# Conectores.net
KiCad netlist of a schematic drawn in Altium Designer
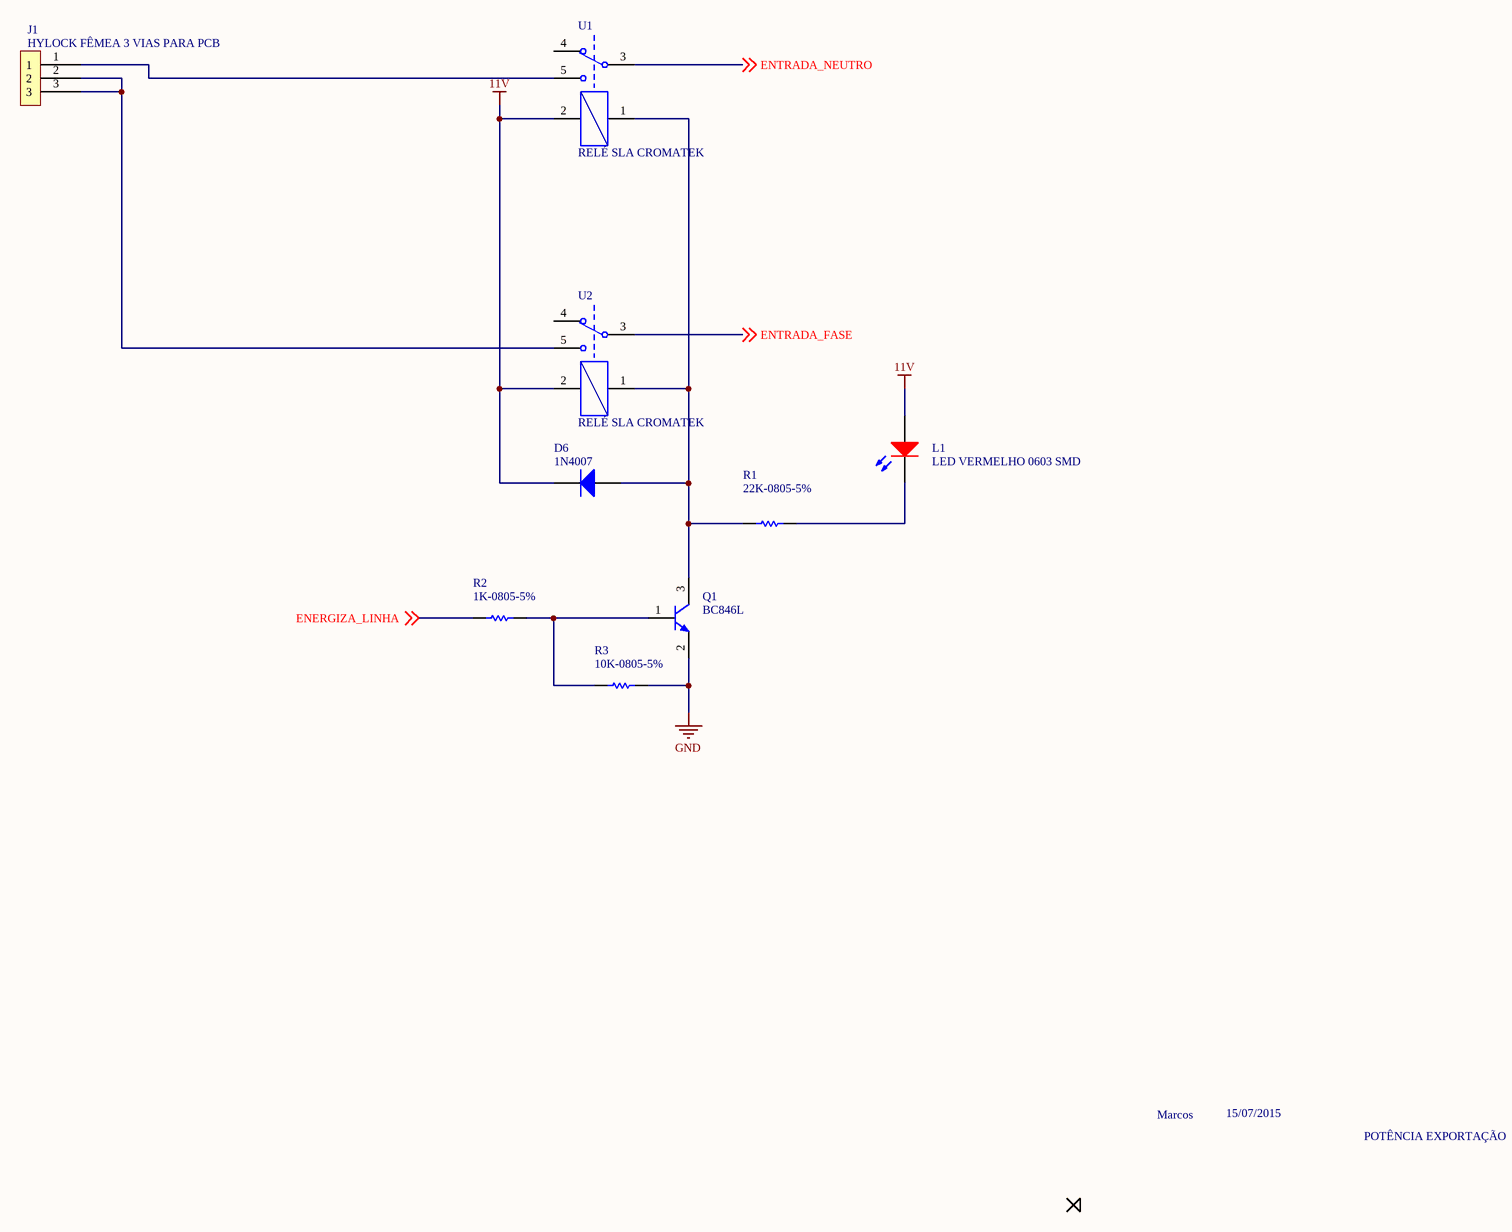
[diagram p0: Conectores.SchDoc]

(export (version "E")
  (design (tool "Eeschema 10.0.6"))
  (components
    (comp (ref "D6") (value "1N4007") (footprint "SMA DIODES") (libsource (lib "AquinoLib") (part "1N4007")))
    (comp (ref "J1")
      (value "HYLOCK FÊMEA 3 VIAS PARA PCB")
      (footprint "CONECTOR HYLOCK 3 VIAS")
      (description "PCMC2-3")
      (libsource (lib "AquinoLib") (part "PCMC2-3"))
    )
    (comp (ref "L1")
      (value "LED VERMELHO 0603 SMD")
      (footprint "LED 1206")
      (libsource (lib "AquinoLib") (part "LED VERMELHO 0603 SMD"))
    )
    (comp (ref "Q1")
      (value "BC846L")
      (footprint "SOT23 - REVISADO ONDA")
      (libsource (lib "AquinoLib") (part "BC846"))
    )
    (comp (ref "R1")
      (value "22K-0805-5%")
      (footprint "0805-REVISADO ONDA")
      (libsource (lib "AquinoLib") (part "22K-0805-5%"))
    )
    (comp (ref "R2")
      (value "1K-0805-5%")
      (footprint "0805-REVISADO ONDA")
      (description "10K-0805-5%")
      (libsource (lib "AquinoLib") (part "10K-0805-5%"))
    )
    (comp (ref "R3")
      (value "10K-0805-5%")
      (footprint "0805-REVISADO ONDA")
      (libsource (lib "AquinoLib") (part "10K-0805-5%"))
    )
    (comp (ref "U1")
      (value "RELÉ SLA CROMATEK")
      (footprint "RELE SLA CROMATEK")
      (libsource (lib "AquinoLib") (part "RELÉ SLA CROMATEK"))
    )
    (comp (ref "U2")
      (value "RELÉ SLA CROMATEK")
      (footprint "RELE SLA CROMATEK")
      (libsource (lib "AquinoLib") (part "RELÉ SLA CROMATEK"))
    )
  )
  (nets
    (net (code "1") (name "11V") (class "Default")
      (node (ref "D6") (pin "2") (pinfunction "K_2") (pintype "passive"))
      (node (ref "L1") (pin "1") (pinfunction "A_1") (pintype "passive"))
      (node (ref "U1") (pin "2") (pinfunction "A2_2") (pintype "passive"))
      (node (ref "U2") (pin "2") (pinfunction "A2_2") (pintype "passive"))
    )
    (net (code "2") (name "ENERGIZA_LINHA") (class "Default")
      (node (ref "R2") (pin "1") (pinfunction "1_1") (pintype "passive"))
    )
    (net (code "3") (name "ENTRADA_FASE") (class "Default")
      (node (ref "U2") (pin "3") (pinfunction "3_3") (pintype "passive"))
    )
    (net (code "4") (name "ENTRADA_NEUTRO") (class "Default")
      (node (ref "U1") (pin "3") (pinfunction "3_3") (pintype "passive"))
    )
    (net (code "5") (name "GND") (class "Default")
      (node (ref "Q1") (pin "2") (pinfunction "E_2") (pintype "passive"))
      (node (ref "R3") (pin "2") (pinfunction "2_2") (pintype "passive"))
    )
    (net (code "6") (name "Net-(D6-A)") (class "Default")
      (node (ref "D6") (pin "1") (pinfunction "A_1") (pintype "passive"))
      (node (ref "Q1") (pin "3") (pinfunction "C_3") (pintype "passive"))
      (node (ref "R1") (pin "1") (pinfunction "1_1") (pintype "passive"))
      (node (ref "U1") (pin "1") (pinfunction "A1_1") (pintype "passive"))
      (node (ref "U2") (pin "1") (pinfunction "A1_1") (pintype "passive"))
    )
    (net (code "7") (name "Net-(J1-Pad1)") (class "Default")
      (node (ref "J1") (pin "1") (pinfunction "1_1") (pintype "passive"))
      (node (ref "U1") (pin "5") (pinfunction "5_5") (pintype "passive"))
    )
    (net (code "8") (name "Net-(J1-Pad2)") (class "Default")
      (node (ref "J1") (pin "2") (pinfunction "2_2") (pintype "passive"))
      (node (ref "J1") (pin "3") (pinfunction "3_3") (pintype "passive"))
      (node (ref "U2") (pin "5") (pinfunction "5_5") (pintype "passive"))
    )
    (net (code "9") (name "Net-(L1-K)") (class "Default")
      (node (ref "L1") (pin "2") (pinfunction "K_2") (pintype "passive"))
      (node (ref "R1") (pin "2") (pinfunction "2_2") (pintype "passive"))
    )
    (net (code "10") (name "Net-(Q1-B)") (class "Default")
      (node (ref "Q1") (pin "1") (pinfunction "B_1") (pintype "passive"))
      (node (ref "R2") (pin "2") (pinfunction "2_2") (pintype "passive"))
      (node (ref "R3") (pin "1") (pinfunction "1_1") (pintype "passive"))
    )
    (net (code "11") (name "unconnected-(U1-Pad4)") (class "Default")
      (node (ref "U1") (pin "4") (pinfunction "4_4") (pintype "passive"))
    )
    (net (code "12") (name "unconnected-(U2-Pad4)") (class "Default")
      (node (ref "U2") (pin "4") (pinfunction "4_4") (pintype "passive"))
    )
  )
)
